# BoardDesign.net
KiCad netlist of a schematic drawn in Altium Designer
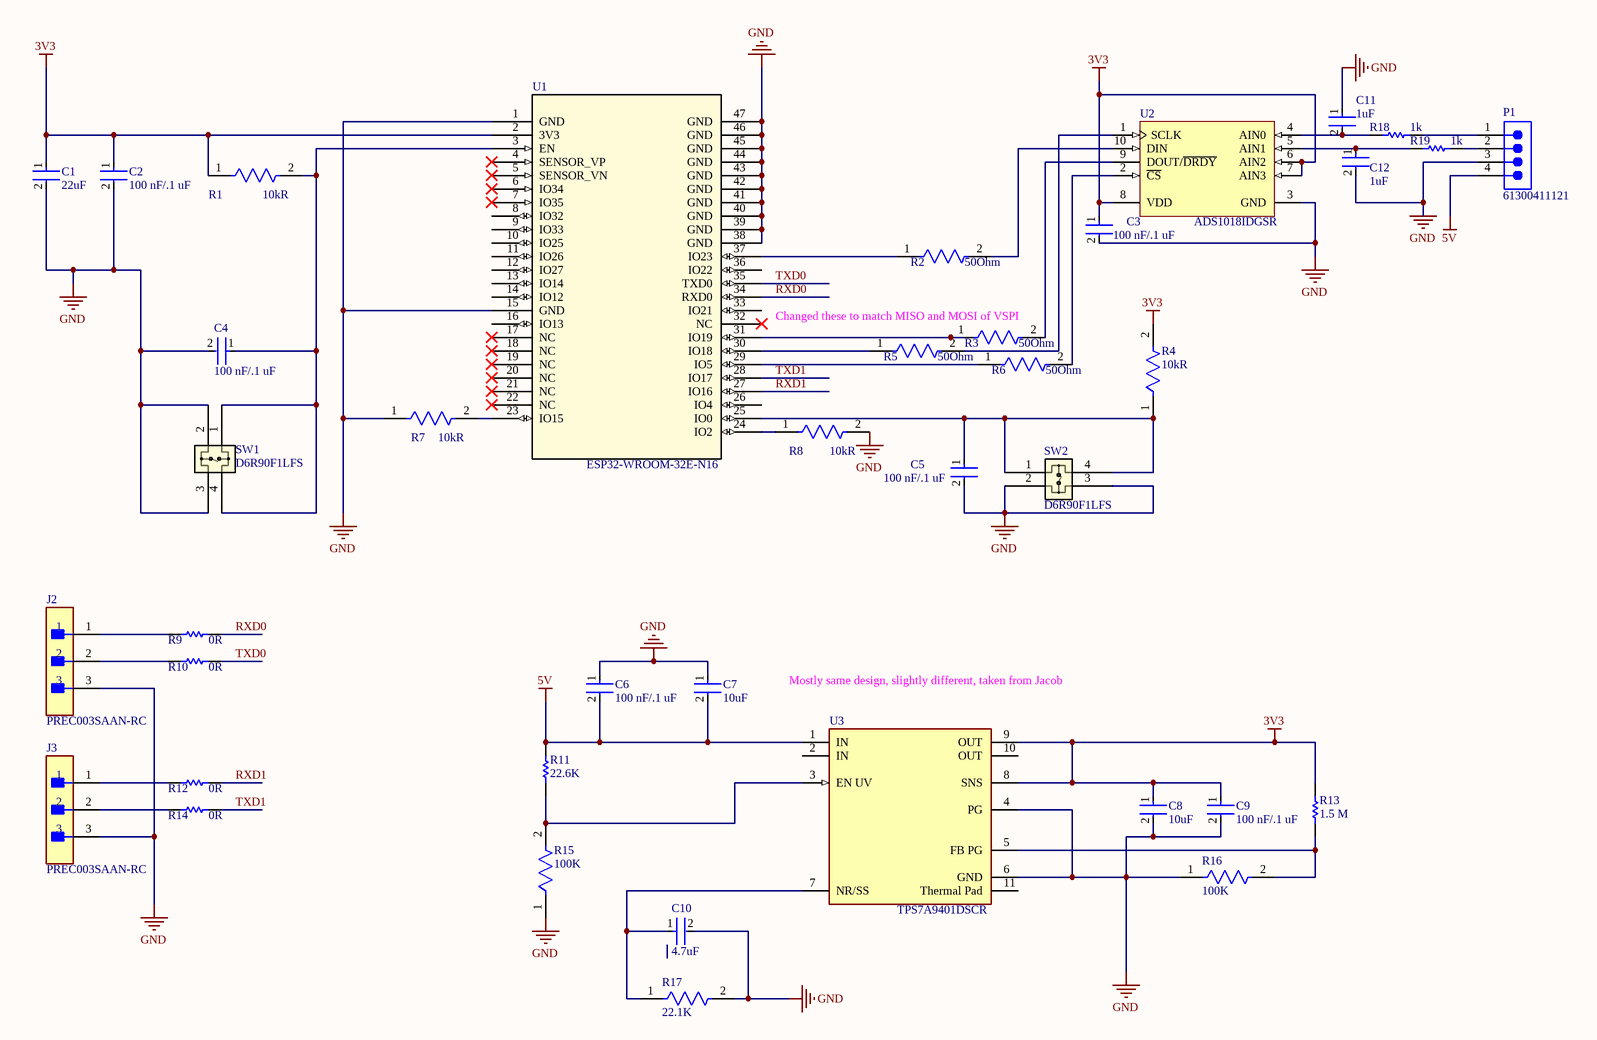
[diagram p0: BoardDesign.SchDoc]

(export (version "E")
  (design (tool "Eeschema 10.0.6"))
  (components
    (comp (ref "C1")
      (value "22uF")
      (footprint "FP-CL21-IPC_A")
      (description "CL21 Series 0805 22uF 6.3V ±20% Tolerance X5R Multilayer Ceramic Chip Capacitor")
      (fields (field (name "TOLERANCE") "20%"))
      (libsource (lib "Altium Content Vault") (part "b4654b650e69147ec39a6b967a45e02"))
    )
    (comp (ref "C2")
      (value "100 nF/.1 uF")
      (footprint "FP-CC0805-0_85-MFG")
      (description "CAP CER 0.1UF 50V X7R 0805")
      (fields (field (name "TOLERANCE") "0.1") (field (name "MANUFACTURER PART NUMBER") "CC0805KRX7R9BB104"))
      (libsource (lib "Altium Content Vault") (part "11868f565c42a9108669ba33697ecf6"))
    )
    (comp (ref "C3")
      (value "100 nF/.1 uF")
      (footprint "FP-CC0805-0_85-MFG")
      (description "CAP CER 0.1UF 50V X7R 0805")
      (fields (field (name "TOLERANCE") "0.1") (field (name "MANUFACTURER PART NUMBER") "CC0805KRX7R9BB104"))
      (libsource (lib "Altium Content Vault") (part "11868f565c42a9108669ba33697ecf6"))
    )
    (comp (ref "C4")
      (value "100 nF/.1 uF")
      (footprint "FP-CC0805-0_85-MFG")
      (description "CAP CER 0.1UF 50V X7R 0805")
      (fields (field (name "TOLERANCE") "0.1") (field (name "MANUFACTURER PART NUMBER") "CC0805KRX7R9BB104"))
      (libsource (lib "Altium Content Vault") (part "11868f565c42a9108669ba33697ecf6"))
    )
    (comp (ref "C5")
      (value "100 nF/.1 uF")
      (footprint "FP-CC0805-0_85-MFG")
      (description "CAP CER 0.1UF 50V X7R 0805")
      (fields (field (name "TOLERANCE") "0.1") (field (name "MANUFACTURER PART NUMBER") "CC0805KRX7R9BB104"))
      (libsource (lib "Altium Content Vault") (part "11868f565c42a9108669ba33697ecf6"))
    )
    (comp (ref "C6")
      (value "100 nF/.1 uF")
      (footprint "FP-CC0805-0_85-MFG")
      (description "CAP CER 0.1UF 50V X7R 0805")
      (fields (field (name "TOLERANCE") "0.1") (field (name "MANUFACTURER PART NUMBER") "CC0805KRX7R9BB104"))
      (libsource (lib "Altium Content Vault") (part "11868f565c42a9108669ba33697ecf6"))
    )
    (comp (ref "C7")
      (value "10uF")
      (footprint "FP-CL21-IPC_B")
      (description "CL21 Series 0805 10uF 16V ±10% Tolerance X5R Multilayer Ceramic Chip Capacitor")
      (fields (field (name "VOLTAGE") "16V") (field (name "TOLERANCE") "10%"))
      (libsource (lib "Altium Content Vault") (part "b4654b650e69147ec39a6b967a45e02"))
    )
    (comp (ref "C8")
      (value "10uF")
      (footprint "FP-CL21-IPC_B")
      (description "CL21 Series 0805 10uF 16V ±10% Tolerance X5R Multilayer Ceramic Chip Capacitor")
      (fields (field (name "VOLTAGE") "16V") (field (name "TOLERANCE") "10%"))
      (libsource (lib "Altium Content Vault") (part "b4654b650e69147ec39a6b967a45e02"))
    )
    (comp (ref "C9")
      (value "100 nF/.1 uF")
      (footprint "FP-CC0805-0_85-MFG")
      (description "CAP CER 0.1UF 50V X7R 0805")
      (fields (field (name "TOLERANCE") "0.1") (field (name "MANUFACTURER PART NUMBER") "CC0805KRX7R9BB104"))
      (libsource (lib "Altium Content Vault") (part "11868f565c42a9108669ba33697ecf6"))
    )
    (comp (ref "C10")
      (value "4.7uF")
      (footprint "FP-CL21-IPC_A")
      (description "CL21 Series 0805 4.7uF 25V ±10% Tolerance X5R Multilayer Ceramic Chip Capacitor")
      (fields (field (name "TOLERANCE") "10%"))
      (libsource (lib "Altium Content Vault") (part "b4654b650e69147ec39a6b967a45e02"))
    )
    (comp (ref "C11")
      (value "1uF")
      (footprint "FP-CC0805-0_85-MFG")
      (description "CAP CER 1UF 16V X7R 0805")
      (fields
        (field (name "MANUFACTURER") "Yageo")
        (field (name "OCTOPART") "https://octopart.com/cc0805kkx7r7bb105-yageo-8376555")
      )
      (libsource (lib "Altium Content Vault") (part "11868f565c42a9108669ba33697ecf6"))
    )
    (comp (ref "C12")
      (value "1uF")
      (footprint "FP-CC0805-0_85-MFG")
      (description "CAP CER 1UF 16V X7R 0805")
      (fields
        (field (name "MANUFACTURER") "Yageo")
        (field (name "OCTOPART") "https://octopart.com/cc0805kkx7r7bb105-yageo-8376555")
      )
      (libsource (lib "Altium Content Vault") (part "11868f565c42a9108669ba33697ecf6"))
    )
    (comp (ref "J2")
      (value "PREC003SAAN-RC")
      (footprint "FP-PREC003SAAN-RC-MFG")
      (description "PREC003SAAN-RC Conn Header Vert 3POS 2.54MM")
      (libsource (lib "Altium Content Vault") (part "0d3f023dd272f625e17a2be33dea85f"))
    )
    (comp (ref "J3")
      (value "PREC003SAAN-RC")
      (footprint "FP-PREC003SAAN-RC-MFG")
      (description "PREC003SAAN-RC Conn Header Vert 3POS 2.54MM")
      (libsource (lib "Altium Content Vault") (part "0d3f023dd272f625e17a2be33dea85f"))
    )
    (comp (ref "P1")
      (value "61300411121")
      (footprint "61300411121")
      (libsource (lib "Altium Content Vault") (part "Header_Male_1R_04P"))
    )
    (comp (ref "R1")
      (value "10kR")
      (footprint "FP-RR1220-IPC_A")
      (description "10kΩ ±0.5% 0.1W 1/10W Chip Resistor 0805 (2012 Metric) Thin Film")
      (fields (field (name "TOLERANCE") "0.5%"))
      (libsource (lib "Altium Content Vault") (part "1029c3af85768c4190bb7ad29bc67b5"))
    )
    (comp (ref "R2")
      (value "50Ohm")
      (footprint "FP-D12-CRCW0805-MFG")
      (description "CRCW080550R0FKTA Res Thick Film 0805 50 Ohm 1% 0.125W(1/8W) ±100ppm/C Pad SMD Automotive T/R")
      (fields (field (name "TOLERANCE") "1%"))
      (libsource (lib "Altium Content Vault") (part "1029c3af85768c4190bb7ad29bc67b5"))
    )
    (comp (ref "R3")
      (value "50Ohm")
      (footprint "FP-D12-CRCW0805-MFG")
      (description "CRCW080550R0FKTA Res Thick Film 0805 50 Ohm 1% 0.125W(1/8W) ±100ppm/C Pad SMD Automotive T/R")
      (fields (field (name "TOLERANCE") "1%"))
      (libsource (lib "Altium Content Vault") (part "1029c3af85768c4190bb7ad29bc67b5"))
    )
    (comp (ref "R4")
      (value "10kR")
      (footprint "FP-RR1220-IPC_A")
      (description "10kΩ ±0.5% 0.1W 1/10W Chip Resistor 0805 (2012 Metric) Thin Film")
      (fields (field (name "TOLERANCE") "0.5%"))
      (libsource (lib "Altium Content Vault") (part "1029c3af85768c4190bb7ad29bc67b5"))
    )
    (comp (ref "R5")
      (value "50Ohm")
      (footprint "FP-D12-CRCW0805-MFG")
      (description "CRCW080550R0FKTA Res Thick Film 0805 50 Ohm 1% 0.125W(1/8W) ±100ppm/C Pad SMD Automotive T/R")
      (fields (field (name "TOLERANCE") "1%"))
      (libsource (lib "Altium Content Vault") (part "1029c3af85768c4190bb7ad29bc67b5"))
    )
    (comp (ref "R6")
      (value "50Ohm")
      (footprint "FP-D12-CRCW0805-MFG")
      (description "CRCW080550R0FKTA Res Thick Film 0805 50 Ohm 1% 0.125W(1/8W) ±100ppm/C Pad SMD Automotive T/R")
      (fields (field (name "TOLERANCE") "1%"))
      (libsource (lib "Altium Content Vault") (part "1029c3af85768c4190bb7ad29bc67b5"))
    )
    (comp (ref "R7")
      (value "10kR")
      (footprint "FP-RR1220-IPC_A")
      (description "10kΩ ±0.5% 0.1W 1/10W Chip Resistor 0805 (2012 Metric) Thin Film")
      (fields (field (name "TOLERANCE") "0.5%"))
      (libsource (lib "Altium Content Vault") (part "1029c3af85768c4190bb7ad29bc67b5"))
    )
    (comp (ref "R8")
      (value "10kR")
      (footprint "FP-RR1220-IPC_A")
      (description "10kΩ ±0.5% 0.1W 1/10W Chip Resistor 0805 (2012 Metric) Thin Film")
      (fields (field (name "TOLERANCE") "0.5%"))
      (libsource (lib "Altium Content Vault") (part "1029c3af85768c4190bb7ad29bc67b5"))
    )
    (comp (ref "R9")
      (value "0R")
      (footprint "RESC2013X70X40NL20T20")
      (description "Chip Resistor, 0 Ohm, +/- 1%, 0.125 W, -55 to 155 degC, 0805 (2012 Metric), RoHS, Tape and Reel")
      (fields (field (name "PARTNUMBER") "ERJ-6GEY0R00V") (field (name "TOLERANCE") "5%"))
      (libsource (lib "Altium Content Vault") (part "RES-2"))
    )
    (comp (ref "R10")
      (value "0R")
      (footprint "RESC2013X70X40NL20T20")
      (description "Chip Resistor, 0 Ohm, +/- 1%, 0.125 W, -55 to 155 degC, 0805 (2012 Metric), RoHS, Tape and Reel")
      (fields (field (name "PARTNUMBER") "ERJ-6GEY0R00V") (field (name "TOLERANCE") "5%"))
      (libsource (lib "Altium Content Vault") (part "RES-2"))
    )
    (comp (ref "R11")
      (value "22.6K")
      (footprint "RESC2013X50X30LL20T20")
      (fields (field (name "MANUFACTURER") "Vishay Dale") (field (name "PART NUMBER") "CRCW080522K6FKEA"))
      (libsource (lib "Altium Content Vault") (part "RES"))
    )
    (comp (ref "R12")
      (value "0R")
      (footprint "RESC2013X70X40NL20T20")
      (description "Chip Resistor, 0 Ohm, +/- 1%, 0.125 W, -55 to 155 degC, 0805 (2012 Metric), RoHS, Tape and Reel")
      (fields (field (name "PARTNUMBER") "ERJ-6GEY0R00V") (field (name "TOLERANCE") "5%"))
      (libsource (lib "Altium Content Vault") (part "RES-2"))
    )
    (comp (ref "R13")
      (value "1.5 M")
      (footprint "RESC0805(2012)_N")
      (description "1M5 0.125W 5% 0805 (2012 Metric)  SMD")
      (fields (field (name "TOLERANCE") "5 %") (field (name "POWER") "0.125 W"))
      (libsource (lib "Altium Content Vault") (part "RES"))
    )
    (comp (ref "R14")
      (value "0R")
      (footprint "RESC2013X70X40NL20T20")
      (description "Chip Resistor, 0 Ohm, +/- 1%, 0.125 W, -55 to 155 degC, 0805 (2012 Metric), RoHS, Tape and Reel")
      (fields (field (name "PARTNUMBER") "ERJ-6GEY0R00V") (field (name "TOLERANCE") "5%"))
      (libsource (lib "Altium Content Vault") (part "RES-2"))
    )
    (comp (ref "R15")
      (value "100K")
      (footprint "FP-RC0805-0_6-IPC_C")
      (description "RES 100K OHM 1% 1/8W 0805")
      (fields (field (name "TOLERANCE") "1%"))
      (libsource (lib "Altium Content Vault") (part "1029c3af85768c4190bb7ad29bc67b5"))
    )
    (comp (ref "R16")
      (value "100K")
      (footprint "FP-RC0805-0_6-IPC_C")
      (description "RES 100K OHM 1% 1/8W 0805")
      (fields (field (name "TOLERANCE") "1%"))
      (libsource (lib "Altium Content Vault") (part "1029c3af85768c4190bb7ad29bc67b5"))
    )
    (comp (ref "R17")
      (value "22.1K")
      (footprint "FP-RMCF0805-IPC_B")
      (description "22.1kΩ ±1% 0.125W 0805 Thick Film Chip Resistor AEC-Q200 compliant")
      (fields (field (name "TOLERANCE") "1%"))
      (libsource (lib "Altium Content Vault") (part "1029c3af85768c4190bb7ad29bc67b5"))
    )
    (comp (ref "R18")
      (value "1k")
      (footprint "RESC2013X60X35ML10T20")
      (description "Chip Resistor, 1 KOhm, +/- 1%, 125 mW, -55 to 155 degC, 0805 (2012 Metric), RoHS, Tape and Reel")
      (fields (field (name "TOLERANCE") "1%") (field (name "MANUFACTURER") "Yageo"))
      (libsource (lib "Altium Content Vault") (part "RES-2"))
    )
    (comp (ref "R19")
      (value "1k")
      (footprint "RESC2013X60X35ML10T20")
      (description "Chip Resistor, 1 KOhm, +/- 1%, 125 mW, -55 to 155 degC, 0805 (2012 Metric), RoHS, Tape and Reel")
      (fields (field (name "TOLERANCE") "1%") (field (name "MANUFACTURER") "Yageo"))
      (libsource (lib "Altium Content Vault") (part "RES-2"))
    )
    (comp (ref "SW1")
      (value "D6R90F1LFS")
      (footprint "D6R_CNK")
      (description "No Description Available")
      (libsource (lib "D6R90F1LFS") (part "D6R90F1LFS"))
    )
    (comp (ref "SW2")
      (value "D6R90F1LFS")
      (footprint "D6R_CNK")
      (description "No Description Available")
      (libsource (lib "") (part "D6R90F1LFS_1"))
    )
    (comp (ref "U1")
      (value "ESP32-WROOM-32E-N16")
      (footprint "ESP32-WROOM-32E_EXP")
      (description "No Description Available")
      (libsource (lib "ESP32-WROOM-32E-N16") (part "ESP32-WROOM-32E-N16"))
    )
    (comp (ref "U2")
      (value "ADS1018IDGSR")
      (footprint "TI-DGS10_N")
      (fields (field (name "MANUFACTURER") "Texas Instruments"))
      (libsource (lib "Altium Content Vault") (part "TI-ADS1X18XXX10"))
    )
    (comp (ref "U3")
      (value "TPS7A9401DSCR")
      (footprint "FP-DSC0010J-MFG")
      (description "1-A, ULTRA-LOW NOISE, ULTRA-HIGH")
      (libsource (lib "Altium Content Vault") (part "a6308bcaf518fe2c6c22e77077fd2b2"))
    )
  )
  (nets
    (net (code "1") (name "/RXD0") (class "Default")
      (node (ref "R9") (pin "2") (pinfunction "2_2") (pintype "passive"))
      (node (ref "U1") (pin "34") (pinfunction "RXD0_34") (pintype "bidirectional"))
    )
    (net (code "2") (name "/RXD1") (class "Default")
      (node (ref "R12") (pin "2") (pinfunction "2_2") (pintype "passive"))
      (node (ref "U1") (pin "27") (pinfunction "IO16_27") (pintype "bidirectional"))
    )
    (net (code "3") (name "/TXD0") (class "Default")
      (node (ref "R10") (pin "2") (pinfunction "2_2") (pintype "passive"))
      (node (ref "U1") (pin "35") (pinfunction "TXD0_35") (pintype "bidirectional"))
    )
    (net (code "4") (name "/TXD1") (class "Default")
      (node (ref "R14") (pin "2") (pinfunction "2_2") (pintype "passive"))
      (node (ref "U1") (pin "28") (pinfunction "IO17_28") (pintype "bidirectional"))
    )
    (net (code "5") (name "3V3") (class "Default")
      (node (ref "C1") (pin "1") (pinfunction "1_1") (pintype "passive"))
      (node (ref "C2") (pin "1") (pinfunction "1_1") (pintype "passive"))
      (node (ref "C3") (pin "1") (pinfunction "1_1") (pintype "passive"))
      (node (ref "C8") (pin "1") (pinfunction "1_1") (pintype "passive"))
      (node (ref "C9") (pin "1") (pinfunction "1_1") (pintype "passive"))
      (node (ref "R1") (pin "1") (pinfunction "1_1") (pintype "passive"))
      (node (ref "R13") (pin "2") (pinfunction "2_2") (pintype "passive"))
      (node (ref "R4") (pin "2") (pinfunction "2_2") (pintype "passive"))
      (node (ref "U1") (pin "2") (pinfunction "3V3_2") (pintype "power_in"))
      (node (ref "U2") (pin "6") (pinfunction "AIN2_6") (pintype "input"))
      (node (ref "U2") (pin "7") (pinfunction "AIN3_7") (pintype "input"))
      (node (ref "U2") (pin "8") (pinfunction "VDD_8") (pintype "power_in"))
      (node (ref "U3") (pin "8") (pinfunction "SNS_8") (pintype "passive"))
      (node (ref "U3") (pin "9") (pinfunction "OUT_9") (pintype "power_in"))
    )
    (net (code "6") (name "5V") (class "Default")
      (node (ref "C6") (pin "2") (pinfunction "2_2") (pintype "passive"))
      (node (ref "C7") (pin "2") (pinfunction "2_2") (pintype "passive"))
      (node (ref "P1") (pin "4") (pinfunction "4_4") (pintype "passive"))
      (node (ref "R11") (pin "1") (pinfunction "1_1") (pintype "passive"))
      (node (ref "U3") (pin "1") (pinfunction "IN_1") (pintype "power_in"))
    )
    (net (code "7") (name "GND") (class "Default")
      (node (ref "C1") (pin "2") (pinfunction "2_2") (pintype "passive"))
      (node (ref "C10") (pin "2") (pinfunction "2_2") (pintype "passive"))
      (node (ref "C11") (pin "1") (pinfunction "1_1") (pintype "passive"))
      (node (ref "C12") (pin "2") (pinfunction "2_2") (pintype "passive"))
      (node (ref "C2") (pin "2") (pinfunction "2_2") (pintype "passive"))
      (node (ref "C3") (pin "2") (pinfunction "2_2") (pintype "passive"))
      (node (ref "C4") (pin "2") (pinfunction "2_2") (pintype "passive"))
      (node (ref "C5") (pin "2") (pinfunction "2_2") (pintype "passive"))
      (node (ref "C6") (pin "1") (pinfunction "1_1") (pintype "passive"))
      (node (ref "C7") (pin "1") (pinfunction "1_1") (pintype "passive"))
      (node (ref "C8") (pin "2") (pinfunction "2_2") (pintype "passive"))
      (node (ref "C9") (pin "2") (pinfunction "2_2") (pintype "passive"))
      (node (ref "J2") (pin "3") (pinfunction "3_3") (pintype "passive"))
      (node (ref "J3") (pin "3") (pinfunction "3_3") (pintype "passive"))
      (node (ref "P1") (pin "3") (pinfunction "3_3") (pintype "passive"))
      (node (ref "R15") (pin "1") (pinfunction "1_1") (pintype "passive"))
      (node (ref "R16") (pin "1") (pinfunction "1_1") (pintype "passive"))
      (node (ref "R17") (pin "2") (pinfunction "2_2") (pintype "passive"))
      (node (ref "R7") (pin "1") (pinfunction "1_1") (pintype "passive"))
      (node (ref "R8") (pin "2") (pinfunction "2_2") (pintype "passive"))
      (node (ref "SW1") (pin "2") (pinfunction "2_2") (pintype "passive"))
      (node (ref "SW1") (pin "3") (pinfunction "3_3") (pintype "passive"))
      (node (ref "SW2") (pin "2") (pinfunction "2_2") (pintype "passive"))
      (node (ref "SW2") (pin "3") (pinfunction "3_3") (pintype "passive"))
      (node (ref "U1") (pin "1") (pinfunction "GND_1") (pintype "power_in"))
      (node (ref "U1") (pin "15") (pinfunction "GND_15") (pintype "power_in"))
      (node (ref "U1") (pin "38") (pinfunction "GND_38") (pintype "power_in"))
      (node (ref "U1") (pin "39") (pinfunction "GND_39") (pintype "power_in"))
      (node (ref "U1") (pin "40") (pinfunction "GND_40") (pintype "power_in"))
      (node (ref "U1") (pin "41") (pinfunction "GND_41") (pintype "power_in"))
      (node (ref "U1") (pin "42") (pinfunction "GND_42") (pintype "power_in"))
      (node (ref "U1") (pin "43") (pinfunction "GND_43") (pintype "power_in"))
      (node (ref "U1") (pin "44") (pinfunction "GND_44") (pintype "power_in"))
      (node (ref "U1") (pin "45") (pinfunction "GND_45") (pintype "power_in"))
      (node (ref "U1") (pin "46") (pinfunction "GND_46") (pintype "power_in"))
      (node (ref "U1") (pin "47") (pinfunction "GND_47") (pintype "power_in"))
      (node (ref "U2") (pin "3") (pinfunction "GND_3") (pintype "power_in"))
      (node (ref "U3") (pin "4") (pinfunction "PG_4") (pintype "open_collector"))
      (node (ref "U3") (pin "6") (pinfunction "GND_6") (pintype "power_in"))
    )
    (net (code "8") (name "Net-(J2-Pad1)") (class "Default")
      (node (ref "J2") (pin "1") (pinfunction "1_1") (pintype "passive"))
      (node (ref "R9") (pin "1") (pinfunction "1_1") (pintype "passive"))
    )
    (net (code "9") (name "Net-(J2-Pad2)") (class "Default")
      (node (ref "J2") (pin "2") (pinfunction "2_2") (pintype "passive"))
      (node (ref "R10") (pin "1") (pinfunction "1_1") (pintype "passive"))
    )
    (net (code "10") (name "Net-(J3-Pad1)") (class "Default")
      (node (ref "J3") (pin "1") (pinfunction "1_1") (pintype "passive"))
      (node (ref "R12") (pin "1") (pinfunction "1_1") (pintype "passive"))
    )
    (net (code "11") (name "Net-(J3-Pad2)") (class "Default")
      (node (ref "J3") (pin "2") (pinfunction "2_2") (pintype "passive"))
      (node (ref "R14") (pin "1") (pinfunction "1_1") (pintype "passive"))
    )
    (net (code "12") (name "Net-(P1-Pad1)") (class "Default")
      (node (ref "P1") (pin "1") (pinfunction "1_1") (pintype "passive"))
      (node (ref "R18") (pin "2") (pinfunction "2_2") (pintype "passive"))
    )
    (net (code "13") (name "Net-(P1-Pad2)") (class "Default")
      (node (ref "P1") (pin "2") (pinfunction "2_2") (pintype "passive"))
      (node (ref "R19") (pin "2") (pinfunction "2_2") (pintype "passive"))
    )
    (net (code "14") (name "Net-(U1-EN)") (class "Default")
      (node (ref "C4") (pin "1") (pinfunction "1_1") (pintype "passive"))
      (node (ref "R1") (pin "2") (pinfunction "2_2") (pintype "passive"))
      (node (ref "SW1") (pin "1") (pinfunction "1_1") (pintype "passive"))
      (node (ref "SW1") (pin "4") (pinfunction "4_4") (pintype "passive"))
      (node (ref "U1") (pin "3") (pinfunction "EN_3") (pintype "input"))
    )
    (net (code "15") (name "Net-(U1-IO0)") (class "Default")
      (node (ref "C5") (pin "1") (pinfunction "1_1") (pintype "passive"))
      (node (ref "R4") (pin "1") (pinfunction "1_1") (pintype "passive"))
      (node (ref "SW2") (pin "1") (pinfunction "1_1") (pintype "passive"))
      (node (ref "SW2") (pin "4") (pinfunction "4_4") (pintype "passive"))
      (node (ref "U1") (pin "25") (pinfunction "IO0_25") (pintype "bidirectional"))
    )
    (net (code "16") (name "Net-(U1-IO2)") (class "Default")
      (node (ref "R8") (pin "1") (pinfunction "1_1") (pintype "passive"))
      (node (ref "U1") (pin "24") (pinfunction "IO2_24") (pintype "bidirectional"))
    )
    (net (code "17") (name "Net-(U1-IO5)") (class "Default")
      (node (ref "R6") (pin "1") (pinfunction "1_1") (pintype "passive"))
      (node (ref "U1") (pin "29") (pinfunction "IO5_29") (pintype "bidirectional"))
    )
    (net (code "18") (name "Net-(U1-IO15)") (class "Default")
      (node (ref "R7") (pin "2") (pinfunction "2_2") (pintype "passive"))
      (node (ref "U1") (pin "23") (pinfunction "IO15_23") (pintype "bidirectional"))
    )
    (net (code "19") (name "Net-(U1-IO18)") (class "Default")
      (node (ref "R5") (pin "1") (pinfunction "1_1") (pintype "passive"))
      (node (ref "U1") (pin "30") (pinfunction "IO18_30") (pintype "bidirectional"))
    )
    (net (code "20") (name "Net-(U1-IO19)") (class "Default")
      (node (ref "R3") (pin "1") (pinfunction "1_1") (pintype "passive"))
      (node (ref "U1") (pin "31") (pinfunction "IO19_31") (pintype "bidirectional"))
    )
    (net (code "21") (name "Net-(U1-IO23)") (class "Default")
      (node (ref "R2") (pin "1") (pinfunction "1_1") (pintype "passive"))
      (node (ref "U1") (pin "37") (pinfunction "IO23_37") (pintype "bidirectional"))
    )
    (net (code "22") (name "Net-(U2-AIN0)") (class "Default")
      (node (ref "C11") (pin "2") (pinfunction "2_2") (pintype "passive"))
      (node (ref "R18") (pin "1") (pinfunction "1_1") (pintype "passive"))
      (node (ref "U2") (pin "4") (pinfunction "AIN0_4") (pintype "input"))
    )
    (net (code "23") (name "Net-(U2-AIN1)") (class "Default")
      (node (ref "C12") (pin "1") (pinfunction "1_1") (pintype "passive"))
      (node (ref "R19") (pin "1") (pinfunction "1_1") (pintype "passive"))
      (node (ref "U2") (pin "5") (pinfunction "AIN1_5") (pintype "input"))
    )
    (net (code "24") (name "Net-(U2-DIN)") (class "Default")
      (node (ref "R2") (pin "2") (pinfunction "2_2") (pintype "passive"))
      (node (ref "U2") (pin "10") (pinfunction "DIN_10") (pintype "input"))
    )
    (net (code "25") (name "Net-(U2-DOUT{slash}~{DRDY})") (class "Default")
      (node (ref "R3") (pin "2") (pinfunction "2_2") (pintype "passive"))
      (node (ref "U2") (pin "9") (pinfunction "DOUT/~{DRDY}_9") (pintype "tri_state"))
    )
    (net (code "26") (name "Net-(U2-SCLK)") (class "Default")
      (node (ref "R5") (pin "2") (pinfunction "2_2") (pintype "passive"))
      (node (ref "U2") (pin "1") (pinfunction "SCLK_1") (pintype "input"))
    )
    (net (code "27") (name "Net-(U2-~{CS})") (class "Default")
      (node (ref "R6") (pin "2") (pinfunction "2_2") (pintype "passive"))
      (node (ref "U2") (pin "2") (pinfunction "~{CS}_2") (pintype "input"))
    )
    (net (code "28") (name "Net-(U3-EN_UV)") (class "Default")
      (node (ref "R11") (pin "2") (pinfunction "2_2") (pintype "passive"))
      (node (ref "R15") (pin "2") (pinfunction "2_2") (pintype "passive"))
      (node (ref "U3") (pin "3") (pinfunction "EN_UV_3") (pintype "input"))
    )
    (net (code "29") (name "Net-(U3-FB_PG)") (class "Default")
      (node (ref "R13") (pin "1") (pinfunction "1_1") (pintype "passive"))
      (node (ref "R16") (pin "2") (pinfunction "2_2") (pintype "passive"))
      (node (ref "U3") (pin "5") (pinfunction "FB_PG_5") (pintype "passive"))
    )
    (net (code "30") (name "Net-(U3-NR{slash}SS)") (class "Default")
      (node (ref "C10") (pin "1") (pinfunction "1_1") (pintype "passive"))
      (node (ref "R17") (pin "1") (pinfunction "1_1") (pintype "passive"))
      (node (ref "U3") (pin "7") (pinfunction "NR/SS_7") (pintype "passive"))
    )
    (net (code "31") (name "unconnected-(U1-IO4-Pad26)") (class "Default")
      (node (ref "U1") (pin "26") (pinfunction "IO4_26") (pintype "bidirectional"))
    )
    (net (code "32") (name "unconnected-(U1-IO12-Pad14)") (class "Default")
      (node (ref "U1") (pin "14") (pinfunction "IO12_14") (pintype "bidirectional"))
    )
    (net (code "33") (name "unconnected-(U1-IO13-Pad16)") (class "Default")
      (node (ref "U1") (pin "16") (pinfunction "IO13_16") (pintype "bidirectional"))
    )
    (net (code "34") (name "unconnected-(U1-IO14-Pad13)") (class "Default")
      (node (ref "U1") (pin "13") (pinfunction "IO14_13") (pintype "bidirectional"))
    )
    (net (code "35") (name "unconnected-(U1-IO21-Pad33)") (class "Default")
      (node (ref "U1") (pin "33") (pinfunction "IO21_33") (pintype "bidirectional"))
    )
    (net (code "36") (name "unconnected-(U1-IO22-Pad36)") (class "Default")
      (node (ref "U1") (pin "36") (pinfunction "IO22_36") (pintype "bidirectional"))
    )
    (net (code "37") (name "unconnected-(U1-IO25-Pad10)") (class "Default")
      (node (ref "U1") (pin "10") (pinfunction "IO25_10") (pintype "bidirectional"))
    )
    (net (code "38") (name "unconnected-(U1-IO26-Pad11)") (class "Default")
      (node (ref "U1") (pin "11") (pinfunction "IO26_11") (pintype "bidirectional"))
    )
    (net (code "39") (name "unconnected-(U1-IO27-Pad12)") (class "Default")
      (node (ref "U1") (pin "12") (pinfunction "IO27_12") (pintype "bidirectional"))
    )
    (net (code "40") (name "unconnected-(U1-IO32-Pad8)") (class "Default")
      (node (ref "U1") (pin "8") (pinfunction "IO32_8") (pintype "bidirectional"))
    )
    (net (code "41") (name "unconnected-(U1-IO33-Pad9)") (class "Default")
      (node (ref "U1") (pin "9") (pinfunction "IO33_9") (pintype "bidirectional"))
    )
    (net (code "42") (name "unconnected-(U1-IO34-Pad6)") (class "Default")
      (node (ref "U1") (pin "6") (pinfunction "IO34_6") (pintype "input+no_connect"))
    )
    (net (code "43") (name "unconnected-(U1-IO35-Pad7)") (class "Default")
      (node (ref "U1") (pin "7") (pinfunction "IO35_7") (pintype "input+no_connect"))
    )
    (net (code "44") (name "unconnected-(U1-NC-Pad17)") (class "Default")
      (node (ref "U1") (pin "17") (pinfunction "NC_17") (pintype "passive+no_connect"))
    )
    (net (code "45") (name "unconnected-(U1-NC-Pad18)") (class "Default")
      (node (ref "U1") (pin "18") (pinfunction "NC_18") (pintype "passive+no_connect"))
    )
    (net (code "46") (name "unconnected-(U1-NC-Pad19)") (class "Default")
      (node (ref "U1") (pin "19") (pinfunction "NC_19") (pintype "passive+no_connect"))
    )
    (net (code "47") (name "unconnected-(U1-NC-Pad20)") (class "Default")
      (node (ref "U1") (pin "20") (pinfunction "NC_20") (pintype "passive+no_connect"))
    )
    (net (code "48") (name "unconnected-(U1-NC-Pad21)") (class "Default")
      (node (ref "U1") (pin "21") (pinfunction "NC_21") (pintype "passive+no_connect"))
    )
    (net (code "49") (name "unconnected-(U1-NC-Pad22)") (class "Default")
      (node (ref "U1") (pin "22") (pinfunction "NC_22") (pintype "passive+no_connect"))
    )
    (net (code "50") (name "unconnected-(U1-NC-Pad32)") (class "Default")
      (node (ref "U1") (pin "32") (pinfunction "NC_32") (pintype "passive+no_connect"))
    )
    (net (code "51") (name "unconnected-(U1-SENSOR_VN-Pad5)") (class "Default")
      (node (ref "U1") (pin "5") (pinfunction "SENSOR_VN_5") (pintype "input+no_connect"))
    )
    (net (code "52") (name "unconnected-(U1-SENSOR_VP-Pad4)") (class "Default")
      (node (ref "U1") (pin "4") (pinfunction "SENSOR_VP_4") (pintype "input+no_connect"))
    )
    (net (code "53") (name "unconnected-(U3-IN-Pad2)") (class "Default")
      (node (ref "U3") (pin "2") (pinfunction "IN_2") (pintype "power_in"))
    )
    (net (code "54") (name "unconnected-(U3-OUT-Pad10)") (class "Default")
      (node (ref "U3") (pin "10") (pinfunction "OUT_10") (pintype "power_in"))
    )
    (net (code "55") (name "unconnected-(U3-Thermal_Pad-Pad11)") (class "Default")
      (node (ref "U3") (pin "11") (pinfunction "Thermal_Pad_11") (pintype "power_in"))
    )
  )
)
